# ESPIOX32_V0_2.net
KiCad netlist of a schematic drawn in EAGLE
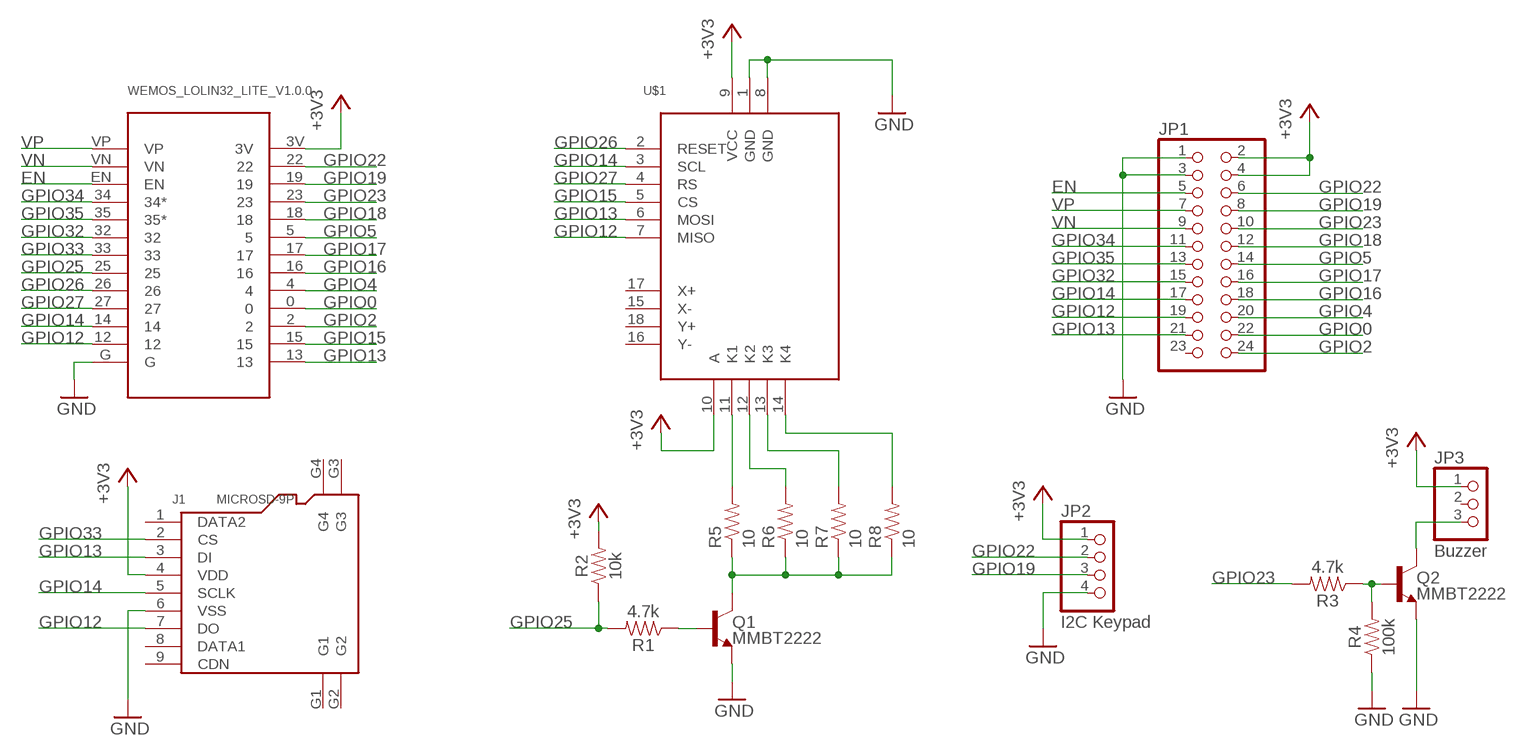
[diagram p0: schematic, sheet 1]

(export (version "E")
  (design (tool "Eeschema 10.0.6"))
  (components
    (comp (ref "J1")
      (value "MICROSD-9P")
      (footprint "eagle-import:MICRO-SD9+4P-SMD-16.1X14.5X1.85MM")
      (libsource (lib "eagle-import") (part "MICRO-SD-CARD-HOLDER-9P"))
    )
    (comp (ref "JP1")
      (value "PINHD-2X12_2.54-SMD")
      (footprint "eagle-import:2X12SMD")
      (libsource (lib "eagle-import") (part "PINHD-2X12_2.54-SMD"))
    )
    (comp (ref "JP2")
      (value "I2C Keypad")
      (footprint "eagle-import:1X04SMD_90")
      (libsource (lib "eagle-import") (part "PINHD-1X04_2.54-SMD-90°"))
    )
    (comp (ref "JP3")
      (value "Buzzer")
      (footprint "eagle-import:1X03SMD_90")
      (libsource (lib "eagle-import") (part "PINHD-1X03_2.54-SMD-90°"))
    )
    (comp (ref "Q1")
      (value "MMBT2222")
      (footprint "eagle-import:SOT23-3")
      (libsource (lib "eagle-import") (part "TRANS_NPN-MMBT2222AL"))
    )
    (comp (ref "Q2")
      (value "MMBT2222")
      (footprint "eagle-import:SOT23-3")
      (libsource (lib "eagle-import") (part "TRANS_NPN-MMBT2222AL"))
    )
    (comp (ref "R1")
      (value "4.7k")
      (footprint "eagle-import:0603")
      (libsource (lib "eagle-import") (part "4.7KOHM-0603-1/10W-1%"))
    )
    (comp (ref "R2")
      (value "10k")
      (footprint "eagle-import:0603")
      (libsource (lib "eagle-import") (part "10KOHM-0603-1/10W-1%"))
    )
    (comp (ref "R3")
      (value "4.7k")
      (footprint "eagle-import:0603")
      (libsource (lib "eagle-import") (part "4.7KOHM-0603-1/10W-1%"))
    )
    (comp (ref "R4")
      (value "100k")
      (footprint "eagle-import:0603")
      (libsource (lib "eagle-import") (part "100KOHM-0603-1/10W-1%"))
    )
    (comp (ref "R5")
      (value "10")
      (footprint "eagle-import:0603-RES")
      (libsource (lib "eagle-import") (part "10OHM-1/10W-5%0603SMD"))
    )
    (comp (ref "R6")
      (value "10")
      (footprint "eagle-import:0603-RES")
      (libsource (lib "eagle-import") (part "10OHM-1/10W-5%0603SMD"))
    )
    (comp (ref "R7")
      (value "10")
      (footprint "eagle-import:0603-RES")
      (libsource (lib "eagle-import") (part "10OHM-1/10W-5%0603SMD"))
    )
    (comp (ref "R8")
      (value "10")
      (footprint "eagle-import:0603-RES")
      (libsource (lib "eagle-import") (part "10OHM-1/10W-5%0603SMD"))
    )
    (comp (ref "U$1")
      (value "18P_3.2IN_TFT_LCD")
      (footprint "eagle-import:18PIN_TFTLCD")
      (libsource (lib "eagle-import") (part "18P_3.2IN_TFT_LCD"))
    )
    (comp (ref "WEMOS_LOLIN32_LITE_V1.0.0")
      (value "WEMOS_LOLIN32_LITE_V1.0.0")
      (footprint "eagle-import:WEMOS_LOLIN32_LITE_V1.0.0")
      (libsource (lib "eagle-import") (part "WEMOS_LOLIN32_LITE_V1.0.0"))
    )
  )
  (nets
    (net (code "1") (name "+3V3") (class "Default")
      (node (ref "J1") (pin "4") (pinfunction "VDD_4") (pintype "bidirectional"))
      (node (ref "JP1") (pin "2") (pinfunction "2_2") (pintype "passive"))
      (node (ref "JP1") (pin "4") (pinfunction "4_4") (pintype "passive"))
      (node (ref "JP2") (pin "1") (pinfunction "1_1") (pintype "passive"))
      (node (ref "JP3") (pin "1") (pinfunction "1_1") (pintype "passive"))
      (node (ref "R2") (pin "2") (pinfunction "2_2") (pintype "passive"))
      (node (ref "U$1") (pin "10") (pinfunction "A_10") (pintype "bidirectional"))
      (node (ref "U$1") (pin "9") (pinfunction "VCC_9") (pintype "bidirectional"))
      (node (ref "WEMOS_LOLIN32_LITE_V1.0.0") (pin "3V") (pinfunction "3V_3V") (pintype "bidirectional"))
    )
    (net (code "2") (name "/EN") (class "Default")
      (node (ref "JP1") (pin "5") (pinfunction "5_5") (pintype "passive"))
      (node (ref "WEMOS_LOLIN32_LITE_V1.0.0") (pin "EN") (pinfunction "EN_EN") (pintype "bidirectional"))
    )
    (net (code "3") (name "/GPIO0") (class "Default")
      (node (ref "JP1") (pin "22") (pinfunction "22_22") (pintype "passive"))
      (node (ref "WEMOS_LOLIN32_LITE_V1.0.0") (pin "0") (pinfunction "0_0") (pintype "bidirectional"))
    )
    (net (code "4") (name "/GPIO2") (class "Default")
      (node (ref "JP1") (pin "24") (pinfunction "24_24") (pintype "passive"))
      (node (ref "WEMOS_LOLIN32_LITE_V1.0.0") (pin "2") (pinfunction "2_2") (pintype "bidirectional"))
    )
    (net (code "5") (name "/GPIO4") (class "Default")
      (node (ref "JP1") (pin "20") (pinfunction "20_20") (pintype "passive"))
      (node (ref "WEMOS_LOLIN32_LITE_V1.0.0") (pin "4") (pinfunction "4_4") (pintype "bidirectional"))
    )
    (net (code "6") (name "/GPIO5") (class "Default")
      (node (ref "JP1") (pin "14") (pinfunction "14_14") (pintype "passive"))
      (node (ref "WEMOS_LOLIN32_LITE_V1.0.0") (pin "5") (pinfunction "5_5") (pintype "bidirectional"))
    )
    (net (code "7") (name "/GPIO12") (class "Default")
      (node (ref "J1") (pin "7") (pinfunction "DO_7") (pintype "bidirectional"))
      (node (ref "JP1") (pin "19") (pinfunction "19_19") (pintype "passive"))
      (node (ref "U$1") (pin "7") (pinfunction "MISO_7") (pintype "bidirectional"))
      (node (ref "WEMOS_LOLIN32_LITE_V1.0.0") (pin "12") (pinfunction "12_12") (pintype "bidirectional"))
    )
    (net (code "8") (name "/GPIO13") (class "Default")
      (node (ref "J1") (pin "3") (pinfunction "DI_3") (pintype "bidirectional"))
      (node (ref "JP1") (pin "21") (pinfunction "21_21") (pintype "passive"))
      (node (ref "U$1") (pin "6") (pinfunction "MOSI_6") (pintype "bidirectional"))
      (node (ref "WEMOS_LOLIN32_LITE_V1.0.0") (pin "13") (pinfunction "13_13") (pintype "bidirectional"))
    )
    (net (code "9") (name "/GPIO14") (class "Default")
      (node (ref "J1") (pin "5") (pinfunction "SCLK_5") (pintype "bidirectional"))
      (node (ref "JP1") (pin "17") (pinfunction "17_17") (pintype "passive"))
      (node (ref "U$1") (pin "3") (pinfunction "SCL_3") (pintype "bidirectional"))
      (node (ref "WEMOS_LOLIN32_LITE_V1.0.0") (pin "14") (pinfunction "14_14") (pintype "bidirectional"))
    )
    (net (code "10") (name "/GPIO15") (class "Default")
      (node (ref "U$1") (pin "5") (pinfunction "CS_5") (pintype "bidirectional"))
      (node (ref "WEMOS_LOLIN32_LITE_V1.0.0") (pin "15") (pinfunction "15_15") (pintype "bidirectional"))
    )
    (net (code "11") (name "/GPIO16") (class "Default")
      (node (ref "JP1") (pin "18") (pinfunction "18_18") (pintype "passive"))
      (node (ref "WEMOS_LOLIN32_LITE_V1.0.0") (pin "16") (pinfunction "16_16") (pintype "bidirectional"))
    )
    (net (code "12") (name "/GPIO17") (class "Default")
      (node (ref "JP1") (pin "16") (pinfunction "16_16") (pintype "passive"))
      (node (ref "WEMOS_LOLIN32_LITE_V1.0.0") (pin "17") (pinfunction "17_17") (pintype "bidirectional"))
    )
    (net (code "13") (name "/GPIO18") (class "Default")
      (node (ref "JP1") (pin "12") (pinfunction "12_12") (pintype "passive"))
      (node (ref "WEMOS_LOLIN32_LITE_V1.0.0") (pin "18") (pinfunction "18_18") (pintype "bidirectional"))
    )
    (net (code "14") (name "/GPIO19") (class "Default")
      (node (ref "JP1") (pin "8") (pinfunction "8_8") (pintype "passive"))
      (node (ref "JP2") (pin "3") (pinfunction "3_3") (pintype "passive"))
      (node (ref "WEMOS_LOLIN32_LITE_V1.0.0") (pin "19") (pinfunction "19_19") (pintype "bidirectional"))
    )
    (net (code "15") (name "/GPIO22") (class "Default")
      (node (ref "JP1") (pin "6") (pinfunction "6_6") (pintype "passive"))
      (node (ref "JP2") (pin "2") (pinfunction "2_2") (pintype "passive"))
      (node (ref "WEMOS_LOLIN32_LITE_V1.0.0") (pin "22") (pinfunction "22_22") (pintype "bidirectional"))
    )
    (net (code "16") (name "/GPIO23") (class "Default")
      (node (ref "JP1") (pin "10") (pinfunction "10_10") (pintype "passive"))
      (node (ref "R3") (pin "2") (pinfunction "2_2") (pintype "passive"))
      (node (ref "WEMOS_LOLIN32_LITE_V1.0.0") (pin "23") (pinfunction "23_23") (pintype "bidirectional"))
    )
    (net (code "17") (name "/GPIO25") (class "Default")
      (node (ref "R1") (pin "2") (pinfunction "2_2") (pintype "passive"))
      (node (ref "R2") (pin "1") (pinfunction "1_1") (pintype "passive"))
      (node (ref "WEMOS_LOLIN32_LITE_V1.0.0") (pin "25") (pinfunction "25_25") (pintype "bidirectional"))
    )
    (net (code "18") (name "/GPIO26") (class "Default")
      (node (ref "U$1") (pin "2") (pinfunction "RESET_2") (pintype "bidirectional"))
      (node (ref "WEMOS_LOLIN32_LITE_V1.0.0") (pin "26") (pinfunction "26_26") (pintype "bidirectional"))
    )
    (net (code "19") (name "/GPIO27") (class "Default")
      (node (ref "U$1") (pin "4") (pinfunction "RS_4") (pintype "bidirectional"))
      (node (ref "WEMOS_LOLIN32_LITE_V1.0.0") (pin "27") (pinfunction "27_27") (pintype "bidirectional"))
    )
    (net (code "20") (name "/GPIO32") (class "Default")
      (node (ref "JP1") (pin "15") (pinfunction "15_15") (pintype "passive"))
      (node (ref "WEMOS_LOLIN32_LITE_V1.0.0") (pin "32") (pinfunction "32_32") (pintype "bidirectional"))
    )
    (net (code "21") (name "/GPIO33") (class "Default")
      (node (ref "J1") (pin "2") (pinfunction "CS_2") (pintype "bidirectional"))
      (node (ref "WEMOS_LOLIN32_LITE_V1.0.0") (pin "33") (pinfunction "33_33") (pintype "bidirectional"))
    )
    (net (code "22") (name "/GPIO34") (class "Default")
      (node (ref "JP1") (pin "11") (pinfunction "11_11") (pintype "passive"))
      (node (ref "WEMOS_LOLIN32_LITE_V1.0.0") (pin "34") (pinfunction "34*_34") (pintype "bidirectional"))
    )
    (net (code "23") (name "/GPIO35") (class "Default")
      (node (ref "JP1") (pin "13") (pinfunction "13_13") (pintype "passive"))
      (node (ref "WEMOS_LOLIN32_LITE_V1.0.0") (pin "35") (pinfunction "35*_35") (pintype "bidirectional"))
    )
    (net (code "24") (name "/VN") (class "Default")
      (node (ref "JP1") (pin "9") (pinfunction "9_9") (pintype "passive"))
      (node (ref "WEMOS_LOLIN32_LITE_V1.0.0") (pin "VN") (pinfunction "VN_VN") (pintype "bidirectional"))
    )
    (net (code "25") (name "/VP") (class "Default")
      (node (ref "JP1") (pin "7") (pinfunction "7_7") (pintype "passive"))
      (node (ref "WEMOS_LOLIN32_LITE_V1.0.0") (pin "VP") (pinfunction "VP_VP") (pintype "bidirectional"))
    )
    (net (code "26") (name "GND") (class "Default")
      (node (ref "J1") (pin "6") (pinfunction "VSS_6") (pintype "bidirectional"))
      (node (ref "JP1") (pin "1") (pinfunction "1_1") (pintype "passive"))
      (node (ref "JP1") (pin "3") (pinfunction "3_3") (pintype "passive"))
      (node (ref "JP2") (pin "4") (pinfunction "4_4") (pintype "passive"))
      (node (ref "Q1") (pin "2") (pinfunction "E_2") (pintype "passive"))
      (node (ref "Q2") (pin "2") (pinfunction "E_2") (pintype "passive"))
      (node (ref "R4") (pin "1") (pinfunction "1_1") (pintype "passive"))
      (node (ref "U$1") (pin "1") (pinfunction "GND_1") (pintype "bidirectional"))
      (node (ref "U$1") (pin "8") (pinfunction "GND_8") (pintype "bidirectional"))
      (node (ref "WEMOS_LOLIN32_LITE_V1.0.0") (pin "G") (pinfunction "G_G") (pintype "bidirectional"))
    )
    (net (code "27") (name "Net-(Q1-B)") (class "Default")
      (node (ref "Q1") (pin "1") (pinfunction "B_1") (pintype "passive"))
      (node (ref "R1") (pin "1") (pinfunction "1_1") (pintype "passive"))
    )
    (net (code "28") (name "Net-(Q1-C)") (class "Default")
      (node (ref "Q1") (pin "3") (pinfunction "C_3") (pintype "passive"))
      (node (ref "R5") (pin "1") (pinfunction "1_1") (pintype "passive"))
      (node (ref "R6") (pin "1") (pinfunction "1_1") (pintype "passive"))
      (node (ref "R7") (pin "1") (pinfunction "1_1") (pintype "passive"))
      (node (ref "R8") (pin "1") (pinfunction "1_1") (pintype "passive"))
    )
    (net (code "29") (name "Net-(Q2-B)") (class "Default")
      (node (ref "Q2") (pin "1") (pinfunction "B_1") (pintype "passive"))
      (node (ref "R3") (pin "1") (pinfunction "1_1") (pintype "passive"))
      (node (ref "R4") (pin "2") (pinfunction "2_2") (pintype "passive"))
    )
    (net (code "30") (name "Net-(Q2-C)") (class "Default")
      (node (ref "JP3") (pin "3") (pinfunction "3_3") (pintype "passive"))
      (node (ref "Q2") (pin "3") (pinfunction "C_3") (pintype "passive"))
    )
    (net (code "31") (name "Net-(U$1-K1)") (class "Default")
      (node (ref "R5") (pin "2") (pinfunction "2_2") (pintype "passive"))
      (node (ref "U$1") (pin "11") (pinfunction "K1_11") (pintype "bidirectional"))
    )
    (net (code "32") (name "Net-(U$1-K2)") (class "Default")
      (node (ref "R6") (pin "2") (pinfunction "2_2") (pintype "passive"))
      (node (ref "U$1") (pin "12") (pinfunction "K2_12") (pintype "bidirectional"))
    )
    (net (code "33") (name "Net-(U$1-K3)") (class "Default")
      (node (ref "R7") (pin "2") (pinfunction "2_2") (pintype "passive"))
      (node (ref "U$1") (pin "13") (pinfunction "K3_13") (pintype "bidirectional"))
    )
    (net (code "34") (name "Net-(U$1-K4)") (class "Default")
      (node (ref "R8") (pin "2") (pinfunction "2_2") (pintype "passive"))
      (node (ref "U$1") (pin "14") (pinfunction "K4_14") (pintype "bidirectional"))
    )
    (net (code "35") (name "unconnected-(J1-CDN-Pad9)") (class "Default")
      (node (ref "J1") (pin "9") (pinfunction "CDN_9") (pintype "bidirectional"))
    )
    (net (code "36") (name "unconnected-(J1-DATA1-Pad8)") (class "Default")
      (node (ref "J1") (pin "8") (pinfunction "DATA1_8") (pintype "bidirectional"))
    )
    (net (code "37") (name "unconnected-(J1-DATA2-Pad1)") (class "Default")
      (node (ref "J1") (pin "1") (pinfunction "DATA2_1") (pintype "bidirectional"))
    )
    (net (code "38") (name "unconnected-(J1-PadG1)") (class "Default")
      (node (ref "J1") (pin "G1") (pinfunction "G1_G1") (pintype "bidirectional"))
    )
    (net (code "39") (name "unconnected-(J1-PadG2)") (class "Default")
      (node (ref "J1") (pin "G2") (pinfunction "G2_G2") (pintype "bidirectional"))
    )
    (net (code "40") (name "unconnected-(J1-PadG3)") (class "Default")
      (node (ref "J1") (pin "G3") (pinfunction "G3_G3") (pintype "bidirectional"))
    )
    (net (code "41") (name "unconnected-(J1-PadG4)") (class "Default")
      (node (ref "J1") (pin "G4") (pinfunction "G4_G4") (pintype "bidirectional"))
    )
    (net (code "42") (name "unconnected-(JP1-Pad23)") (class "Default")
      (node (ref "JP1") (pin "23") (pinfunction "23_23") (pintype "passive"))
    )
    (net (code "43") (name "unconnected-(JP3-Pad2)") (class "Default")
      (node (ref "JP3") (pin "2") (pinfunction "2_2") (pintype "passive"))
    )
    (net (code "44") (name "unconnected-(U$1-X+-Pad17)") (class "Default")
      (node (ref "U$1") (pin "17") (pinfunction "X+_17") (pintype "bidirectional"))
    )
    (net (code "45") (name "unconnected-(U$1-X--Pad15)") (class "Default")
      (node (ref "U$1") (pin "15") (pinfunction "X-_15") (pintype "bidirectional"))
    )
    (net (code "46") (name "unconnected-(U$1-Y+-Pad18)") (class "Default")
      (node (ref "U$1") (pin "18") (pinfunction "Y+_18") (pintype "bidirectional"))
    )
    (net (code "47") (name "unconnected-(U$1-Y--Pad16)") (class "Default")
      (node (ref "U$1") (pin "16") (pinfunction "Y-_16") (pintype "bidirectional"))
    )
  )
)
